# yin_bit.net
KiCad netlist of a schematic drawn in EAGLE
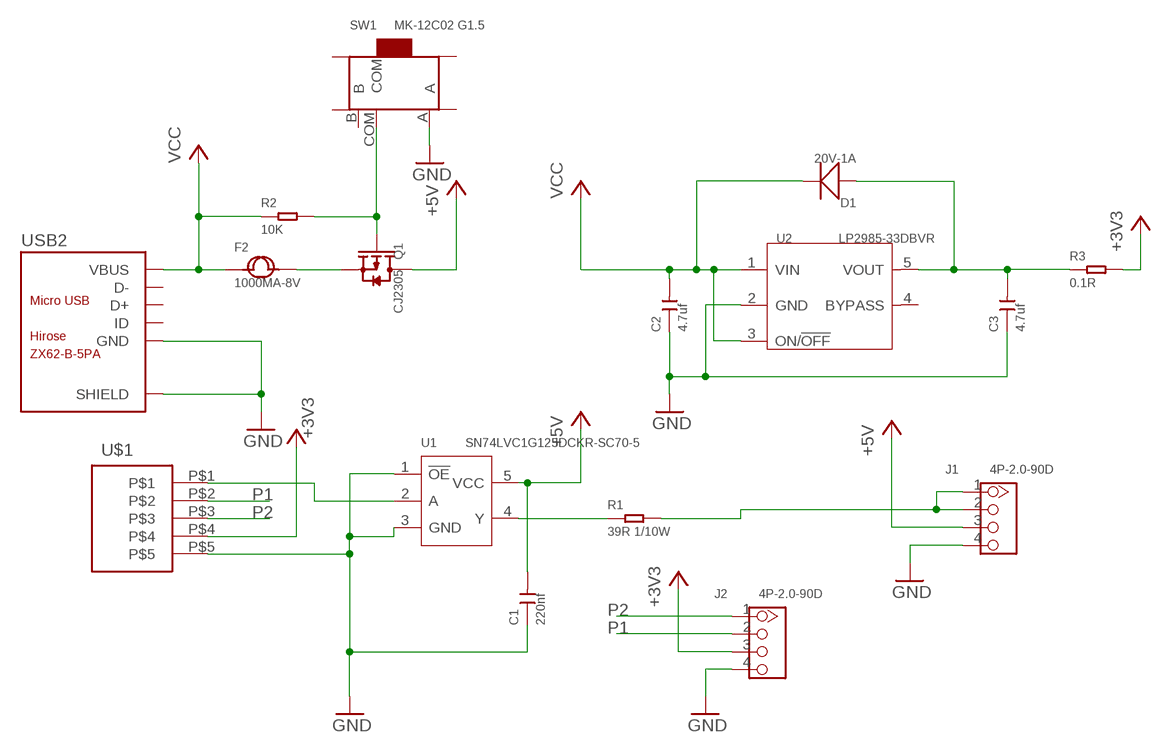
[diagram p0: schematic, sheet 1]

(export (version "E")
  (design (tool "Eeschema 10.0.6"))
  (components
    (comp (ref "C1")
      (value "220nf")
      (footprint "eagle-import:C0603")
      (fields (field (name "MPN") "CC0603KRX7R8BB224"))
      (libsource (lib "eagle-import") (part "CERAMIC-220NF-25V-10%-X7R(0603)"))
    )
    (comp (ref "C2")
      (value "4.7uf")
      (footprint "eagle-import:C0603")
      (fields (field (name "MPN") "CC0603KRX5R6BB475"))
      (libsource (lib "eagle-import") (part "CERAMIC-4.7UF-10V-10%-X5R(0603)"))
    )
    (comp (ref "C3")
      (value "4.7uf")
      (footprint "eagle-import:C0603")
      (fields (field (name "MPN") "CC0603KRX5R6BB475"))
      (libsource (lib "eagle-import") (part "CERAMIC-4.7UF-10V-10%-X5R(0603)"))
    )
    (comp (ref "D1")
      (value "20V-1A")
      (footprint "eagle-import:SOD-123")
      (fields (field (name "MPN") "B5819W"))
      (libsource (lib "eagle-import") (part "SMD-DIODE-SCHOTTKY-20V-1A(SOD-123)"))
    )
    (comp (ref "F2")
      (value "1000MA-8V")
      (footprint "eagle-import:F1206")
      (fields (field (name "MPN") "KT8-1000SMD1206"))
      (libsource (lib "eagle-import") (part "SMD-PPTC-1000MA-8V(1206)"))
    )
    (comp (ref "J1")
      (value "4P-2.0-90D")
      (footprint "eagle-import:HW4-2.0-90D")
      (libsource (lib "eagle-import") (part "GROVE-CONNECTOR-DIP-90D(4P-2.0)"))
    )
    (comp (ref "J2")
      (value "4P-2.0-90D")
      (footprint "eagle-import:HW4-2.0-90D")
      (libsource (lib "eagle-import") (part "GROVE-CONNECTOR-DIP-90D(4P-2.0)"))
    )
    (comp (ref "Q1")
      (value "CJ2305")
      (footprint "eagle-import:SOT-23")
      (libsource (lib "eagle-import") (part "SMD-MOSFET-P-CH-8V-4.1A-CJ2305(SOT-23)"))
    )
    (comp (ref "R1")
      (value "39R 1/10W")
      (footprint "eagle-import:R0603")
      (fields (field (name "MPN") "RC0603JR-0739RL"))
      (libsource (lib "eagle-import") (part "SMD-RES-39R-5%-1/10W(0603)"))
    )
    (comp (ref "R2")
      (value "10K")
      (footprint "eagle-import:R0603")
      (fields (field (name "MPN") "RC0603FR-0710KL"))
      (libsource (lib "eagle-import") (part "SMD-RES-10K-1%-1/10W(0603)"))
    )
    (comp (ref "R3")
      (value "0.1R")
      (footprint "eagle-import:R0805")
      (fields (field (name "MPN") "RL0805JR-070R1L"))
      (libsource (lib "eagle-import") (part "SMD-RES-0.1R-5%-1/8W(0805)"))
    )
    (comp (ref "SW1")
      (value "MK-12C02 G1.5")
      (footprint "eagle-import:SW7-SMD-L6.7X2.7X3.2MM")
      (libsource (lib "eagle-import") (part "SMD-TOGGLE-SWITCH-ON-ON(3+4P-6.7X2.7MM)"))
    )
    (comp (ref "U$1")
      (value "MICROBIT-HOLL")
      (footprint "eagle-import:MICROBIT-HOLL")
      (libsource (lib "eagle-import") (part "MICROBIT-HOLL"))
    )
    (comp (ref "U1")
      (value "SN74LVC1G125DCKR-SC70-5")
      (footprint "eagle-import:SC-70-5")
      (fields (field (name "MPN") "SN74LVC1G125DCKR"))
      (libsource (lib "eagle-import") (part "LOGIC-SN74LVC1G125DCKR(SC70-5)"))
    )
    (comp (ref "U2")
      (value "LP2985-33DBVR")
      (footprint "eagle-import:SOT-23-5")
      (libsource (lib "eagle-import") (part "PMIC-LP2985-33DBVR(SOT23-5)"))
    )
    (comp (ref "USB2")
      (value "ZX62-B-5PA")
      (footprint "eagle-import:MICRO-USB5+6P-SMD-0.65-AB")
      (libsource (lib "eagle-import") (part "MICRO-USB-SMD(ZX62-B-5PA)"))
    )
  )
  (nets
    (net (code "1") (name "+3V3") (class "Default")
      (node (ref "J2") (pin "3") (pinfunction "3_3") (pintype "bidirectional"))
      (node (ref "R3") (pin "2") (pinfunction "2_2") (pintype "passive"))
      (node (ref "U$1") (pin "P$4") (pinfunction "P$4_P$4") (pintype "bidirectional"))
    )
    (net (code "2") (name "+5V") (class "Default")
      (node (ref "C1") (pin "2") (pinfunction "2_2") (pintype "passive"))
      (node (ref "J1") (pin "3") (pinfunction "3_3") (pintype "bidirectional"))
      (node (ref "Q1") (pin "3") (pinfunction "D_3") (pintype "passive"))
      (node (ref "U1") (pin "5") (pinfunction "VCC_5") (pintype "bidirectional"))
    )
    (net (code "3") (name "/P1") (class "Default")
      (node (ref "J2") (pin "2") (pinfunction "2_2") (pintype "bidirectional"))
      (node (ref "U$1") (pin "P$2") (pinfunction "P$2_P$2") (pintype "bidirectional"))
    )
    (net (code "4") (name "/P2") (class "Default")
      (node (ref "J2") (pin "1") (pinfunction "1_1") (pintype "bidirectional"))
      (node (ref "U$1") (pin "P$3") (pinfunction "P$3_P$3") (pintype "bidirectional"))
    )
    (net (code "5") (name "GND") (class "Default")
      (node (ref "C1") (pin "1") (pinfunction "1_1") (pintype "passive"))
      (node (ref "C2") (pin "1") (pinfunction "1_1") (pintype "passive"))
      (node (ref "C3") (pin "1") (pinfunction "1_1") (pintype "passive"))
      (node (ref "J1") (pin "4") (pinfunction "4_4") (pintype "bidirectional"))
      (node (ref "J2") (pin "4") (pinfunction "4_4") (pintype "bidirectional"))
      (node (ref "SW1") (pin "A") (pinfunction "A_A") (pintype "bidirectional"))
      (node (ref "U$1") (pin "P$5") (pinfunction "P$5_P$5") (pintype "bidirectional"))
      (node (ref "U1") (pin "1") (pinfunction "~{OE}_1") (pintype "bidirectional"))
      (node (ref "U1") (pin "3") (pinfunction "GND_3") (pintype "bidirectional"))
      (node (ref "U2") (pin "2") (pinfunction "GND_2") (pintype "bidirectional"))
      (node (ref "USB2") (pin "5") (pinfunction "GND_5") (pintype "power_in"))
      (node (ref "USB2") (pin "P1") (pinfunction "SHIELD_P1") (pintype "power_in"))
      (node (ref "USB2") (pin "P2") (pinfunction "SHIELD_P2") (pintype "power_in"))
      (node (ref "USB2") (pin "P3") (pinfunction "SHIELD_P3") (pintype "power_in"))
      (node (ref "USB2") (pin "P4") (pinfunction "SHIELD_P4") (pintype "power_in"))
      (node (ref "USB2") (pin "P5") (pinfunction "SHIELD_P5") (pintype "power_in"))
      (node (ref "USB2") (pin "P6") (pinfunction "SHIELD_P6") (pintype "power_in"))
    )
    (net (code "6") (name "Net-(J1-Pad1)") (class "Default")
      (node (ref "J1") (pin "1") (pinfunction "1_1") (pintype "bidirectional"))
      (node (ref "J1") (pin "2") (pinfunction "2_2") (pintype "bidirectional"))
      (node (ref "R1") (pin "2") (pinfunction "2_2") (pintype "passive"))
    )
    (net (code "7") (name "Net-(Q1-G)") (class "Default")
      (node (ref "Q1") (pin "1") (pinfunction "G_1") (pintype "passive"))
      (node (ref "R2") (pin "2") (pinfunction "2_2") (pintype "passive"))
      (node (ref "SW1") (pin "COM") (pinfunction "COM_COM") (pintype "bidirectional"))
    )
    (net (code "8") (name "Net-(Q1-S)") (class "Default")
      (node (ref "F2") (pin "2") (pinfunction "2_2") (pintype "bidirectional"))
      (node (ref "Q1") (pin "2") (pinfunction "S_2") (pintype "passive"))
    )
    (net (code "9") (name "Net-(U1-A)") (class "Default")
      (node (ref "U$1") (pin "P$1") (pinfunction "P$1_P$1") (pintype "bidirectional"))
      (node (ref "U1") (pin "2") (pinfunction "A_2") (pintype "bidirectional"))
    )
    (net (code "10") (name "Net-(U1-Y)") (class "Default")
      (node (ref "R1") (pin "1") (pinfunction "1_1") (pintype "passive"))
      (node (ref "U1") (pin "4") (pinfunction "Y_4") (pintype "bidirectional"))
    )
    (net (code "11") (name "Net-(U2-VOUT)") (class "Default")
      (node (ref "C3") (pin "2") (pinfunction "2_2") (pintype "passive"))
      (node (ref "D1") (pin "+") (pinfunction "+_+") (pintype "passive"))
      (node (ref "R3") (pin "1") (pinfunction "1_1") (pintype "passive"))
      (node (ref "U2") (pin "5") (pinfunction "VOUT_5") (pintype "bidirectional"))
    )
    (net (code "12") (name "VCC") (class "Default")
      (node (ref "C2") (pin "2") (pinfunction "2_2") (pintype "passive"))
      (node (ref "D1") (pin "-") (pinfunction "-_-") (pintype "passive"))
      (node (ref "F2") (pin "1") (pinfunction "1_1") (pintype "bidirectional"))
      (node (ref "R2") (pin "1") (pinfunction "1_1") (pintype "passive"))
      (node (ref "U2") (pin "1") (pinfunction "VIN_1") (pintype "bidirectional"))
      (node (ref "U2") (pin "3") (pinfunction "ON/~{OFF}_3") (pintype "bidirectional"))
      (node (ref "USB2") (pin "1") (pinfunction "VBUS_1") (pintype "power_in"))
    )
    (net (code "13") (name "unconnected-(SW1-PadB)") (class "Default")
      (node (ref "SW1") (pin "B") (pinfunction "B_B") (pintype "bidirectional"))
    )
    (net (code "14") (name "unconnected-(SW1-PadSS1)") (class "Default")
      (node (ref "SW1") (pin "SS1") (pinfunction "SS1_SS1") (pintype "bidirectional"))
    )
    (net (code "15") (name "unconnected-(SW1-PadSS2)") (class "Default")
      (node (ref "SW1") (pin "SS2") (pinfunction "SS2_SS2") (pintype "bidirectional"))
    )
    (net (code "16") (name "unconnected-(SW1-PadSS3)") (class "Default")
      (node (ref "SW1") (pin "SS3") (pinfunction "SS3_SS3") (pintype "bidirectional"))
    )
    (net (code "17") (name "unconnected-(SW1-PadSS4)") (class "Default")
      (node (ref "SW1") (pin "SS4") (pinfunction "SS4_SS4") (pintype "bidirectional"))
    )
    (net (code "18") (name "unconnected-(U2-BYPASS-Pad4)") (class "Default")
      (node (ref "U2") (pin "4") (pinfunction "BYPASS_4") (pintype "bidirectional"))
    )
    (net (code "19") (name "unconnected-(USB2-D+-Pad3)") (class "Default")
      (node (ref "USB2") (pin "3") (pinfunction "D+_3") (pintype "bidirectional"))
    )
    (net (code "20") (name "unconnected-(USB2-D--Pad2)") (class "Default")
      (node (ref "USB2") (pin "2") (pinfunction "D-_2") (pintype "bidirectional"))
    )
    (net (code "21") (name "unconnected-(USB2-ID-Pad4)") (class "Default")
      (node (ref "USB2") (pin "4") (pinfunction "ID_4") (pintype "bidirectional"))
    )
  )
)
